# Mechanics.net
KiCad netlist of a schematic drawn in Altium Designer
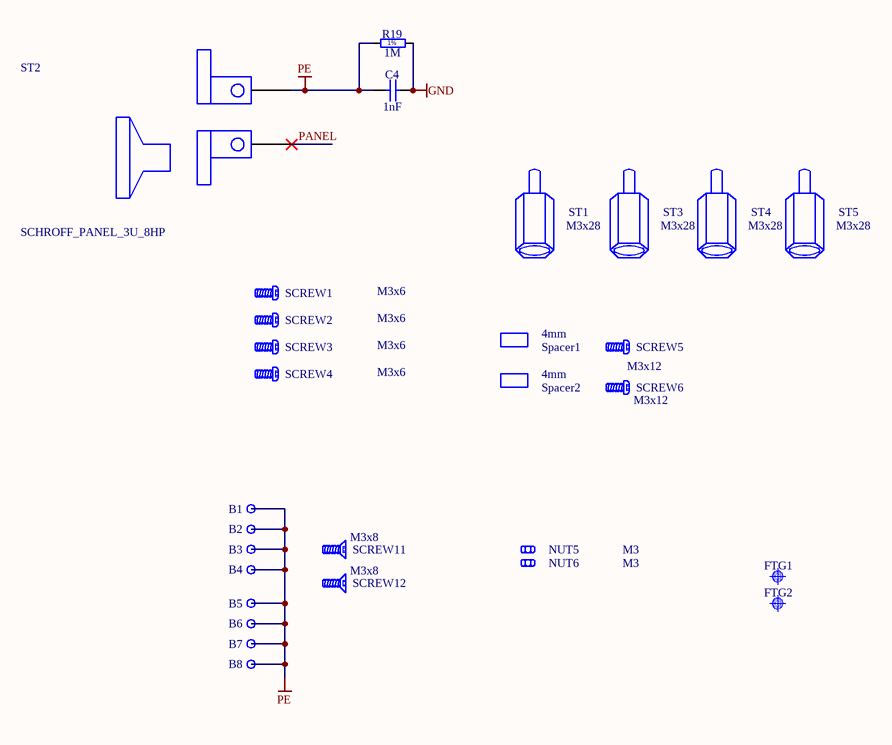
[diagram p0: Mechanics.SchDoc]

(export (version "E")
  (design (tool "Eeschema 10.0.6"))
  (components
    (comp (ref "B1")
      (value "Plated Hole")
      (footprint "MTG320_700")
      (description "Single Terminal Socket")
      (fields (field (name "PART NUMBER") "PLATED_HOLE3.2_PAD7.0") (field (name "AUTHOR") "CERN DEM JMW"))
      (libsource (lib "Eletro-mechanical") (part "Single Terminal Socket"))
    )
    (comp (ref "B2")
      (value "Plated Hole")
      (footprint "MTG320_700")
      (description "Single Terminal Socket")
      (fields (field (name "PART NUMBER") "PLATED_HOLE3.2_PAD7.0") (field (name "AUTHOR") "CERN DEM JMW"))
      (libsource (lib "Eletro-mechanical") (part "Single Terminal Socket"))
    )
    (comp (ref "B3")
      (value "Plated Hole")
      (footprint "MTG320_700")
      (description "Single Terminal Socket")
      (fields (field (name "PART NUMBER") "PLATED_HOLE3.2_PAD7.0") (field (name "AUTHOR") "CERN DEM JMW"))
      (libsource (lib "Eletro-mechanical") (part "Single Terminal Socket"))
    )
    (comp (ref "B4")
      (value "Plated Hole")
      (footprint "MTG320_700")
      (description "Single Terminal Socket")
      (fields (field (name "PART NUMBER") "PLATED_HOLE3.2_PAD7.0") (field (name "AUTHOR") "CERN DEM JMW"))
      (libsource (lib "Eletro-mechanical") (part "Single Terminal Socket"))
    )
    (comp (ref "B5")
      (value "Plated Hole")
      (footprint "MTG350_650")
      (description "Single Terminal Socket")
      (fields (field (name "PART NUMBER") "PLATED_HOLE3.5_PAD6.5") (field (name "AUTHOR") "CERN DEM JLC"))
      (libsource (lib "Eletro-mechanical") (part "Single Terminal Socket"))
    )
    (comp (ref "B6")
      (value "Plated Hole")
      (footprint "MTG350_650")
      (description "Single Terminal Socket")
      (fields (field (name "PART NUMBER") "PLATED_HOLE3.5_PAD6.5") (field (name "AUTHOR") "CERN DEM JLC"))
      (libsource (lib "Eletro-mechanical") (part "Single Terminal Socket"))
    )
    (comp (ref "B7")
      (value "Plated Hole")
      (footprint "MTG350_650")
      (description "Single Terminal Socket")
      (fields (field (name "PART NUMBER") "PLATED_HOLE3.5_PAD6.5") (field (name "AUTHOR") "CERN DEM JLC"))
      (libsource (lib "Eletro-mechanical") (part "Single Terminal Socket"))
    )
    (comp (ref "B8")
      (value "Plated Hole")
      (footprint "MTG350_650")
      (description "Single Terminal Socket")
      (fields (field (name "PART NUMBER") "PLATED_HOLE3.5_PAD6.5") (field (name "AUTHOR") "CERN DEM JLC"))
      (libsource (lib "Eletro-mechanical") (part "Single Terminal Socket"))
    )
    (comp (ref "C4")
      (value "1nF")
      (footprint "CAPC3216X180N")
      (description "Non-polarised capacitor")
      (fields
        (field (name "PART NUMBER") "CC1206_1NF_2KV_10%_X7R")
        (field (name "VOLTAGE") "2kV")
        (field (name "AUTHOR") "CERN DEM JLC")
      )
      (libsource (lib "Capacitors") (part "Capacitor - non polarized"))
    )
    (comp (ref "FTG1")
      (value "Use only in PCB")
      (footprint "FIDUCIAL_TOP_C100-200")
      (description "Fiducial Target")
      (fields (field (name "PART NUMBER") "FIDUCIAL_TARGET_C100-200") (field (name "AUTHOR") "CERN DEM JLC"))
      (libsource (lib "Eletro-mechanical") (part "Fiducial Target"))
    )
    (comp (ref "FTG2")
      (value "Use only in PCB")
      (footprint "FIDUCIAL_TOP_S100-200")
      (description "Fiducial Target")
      (fields (field (name "PART NUMBER") "FIDUCIAL_TARGET_S100-200") (field (name "AUTHOR") "CERN DEM JLC"))
      (libsource (lib "Eletro-mechanical") (part "Fiducial Target"))
    )
    (comp (ref "NUT5")
      (value "M3")
      (footprint "BOSSARD_BN628-1241443_v")
      (description "Nut")
      (fields
        (field (name "PART NUMBER") "BOSSARD_BN628-1241443_v")
        (field (name "MANUFACTURER") "BOSSARD")
        (field (name "AUTHOR") "CERN DEM JMW")
      )
      (libsource (lib "Eletro-mechanical") (part "Nut"))
    )
    (comp (ref "NUT6")
      (value "M3")
      (footprint "BOSSARD_BN628-1241443_v")
      (description "Nut")
      (fields
        (field (name "PART NUMBER") "BOSSARD_BN628-1241443_v")
        (field (name "MANUFACTURER") "BOSSARD")
        (field (name "AUTHOR") "CERN DEM JMW")
      )
      (libsource (lib "Eletro-mechanical") (part "Nut"))
    )
    (comp (ref "R19")
      (value "1M")
      (footprint "RESC3216X65N")
      (description "Resistor - 1%")
      (fields
        (field (name "PART NUMBER") "R1206_1M_1%_0.25W_100PPM")
        (field (name "POWER") "0.25W")
        (field (name "AUTHOR") "CERN DEM JLC")
      )
      (libsource (lib "Resistors") (part "Resistor - 1%"))
    )
    (comp (ref "SCREW1")
      (value "M3x6")
      (footprint "BOSSARD_BN5687-3061605_v")
      (description "Screw")
      (fields
        (field (name "PART NUMBER") "BOSSARD_BN5687-3061605_v")
        (field (name "MANUFACTURER") "BOSSARD")
        (field (name "AUTHOR") "CERN DEM JLC")
      )
      (libsource (lib "Eletro-mechanical") (part "Screw"))
    )
    (comp (ref "SCREW2")
      (value "M3x6")
      (footprint "BOSSARD_BN5687-3061605_v")
      (description "Screw")
      (fields
        (field (name "PART NUMBER") "BOSSARD_BN5687-3061605_v")
        (field (name "MANUFACTURER") "BOSSARD")
        (field (name "AUTHOR") "CERN DEM JLC")
      )
      (libsource (lib "Eletro-mechanical") (part "Screw"))
    )
    (comp (ref "SCREW3")
      (value "M3x6")
      (footprint "BOSSARD_BN5687-3061605_v")
      (description "Screw")
      (fields
        (field (name "PART NUMBER") "BOSSARD_BN5687-3061605_v")
        (field (name "MANUFACTURER") "BOSSARD")
        (field (name "AUTHOR") "CERN DEM JLC")
      )
      (libsource (lib "Eletro-mechanical") (part "Screw"))
    )
    (comp (ref "SCREW4")
      (value "M3x6")
      (footprint "BOSSARD_BN5687-3061605_v")
      (description "Screw")
      (fields
        (field (name "PART NUMBER") "BOSSARD_BN5687-3061605_v")
        (field (name "MANUFACTURER") "BOSSARD")
        (field (name "AUTHOR") "CERN DEM JLC")
      )
      (libsource (lib "Eletro-mechanical") (part "Screw"))
    )
    (comp (ref "SCREW5")
      (value "M3x12")
      (footprint "BOSSARD_BN5687-3061609_v")
      (description "Screw")
      (fields
        (field (name "PART NUMBER") "BOSSARD_BN5687-3061609_v")
        (field (name "MANUFACTURER") "BOSSARD")
        (field (name "AUTHOR") "CERN DEM JLC")
      )
      (libsource (lib "Eletro-mechanical") (part "Screw"))
    )
    (comp (ref "SCREW6")
      (value "M3x12")
      (footprint "BOSSARD_BN5687-3061609_v")
      (description "Screw")
      (fields
        (field (name "PART NUMBER") "BOSSARD_BN5687-3061609_v")
        (field (name "MANUFACTURER") "BOSSARD")
        (field (name "AUTHOR") "CERN DEM JLC")
      )
      (libsource (lib "Eletro-mechanical") (part "Screw"))
    )
    (comp (ref "SCREW11")
      (value "M3x8")
      (footprint "OSSARD_M3X8/BN3327_h")
      (description "Screw; 3x8; Head: countersunk; Pozidriv; A2 stainless steel")
      (fields
        (field (name "PART NUMBER") "OSSARD_M3X8/BN3327")
        (field (name "MANUFACTURER") "BOSSARD")
        (field (name "AUTHOR") "GK")
      )
      (libsource (lib "Mechanical") (part "Screw_M3x8_Countersunk"))
    )
    (comp (ref "SCREW12")
      (value "M3x8")
      (footprint "OSSARD_M3X8/BN3327_h")
      (description "Screw; 3x8; Head: countersunk; Pozidriv; A2 stainless steel")
      (fields
        (field (name "PART NUMBER") "OSSARD_M3X8/BN3327")
        (field (name "MANUFACTURER") "BOSSARD")
        (field (name "AUTHOR") "GK")
      )
      (libsource (lib "Mechanical") (part "Screw_M3x8_Countersunk"))
    )
    (comp (ref "Spacer1")
      (value "4mm")
      (footprint "DREMEC_DR316/3.2X4")
      (fields
        (field (name "PART NUMBER") "DREMEC_DR316/3.2X4")
        (field (name "MANUFACTURER") "DREMEC")
        (field (name "MANUFACTURER PART NUMBER") "DR316/3.2X4")
        (field (name "AUTHOR") "GK")
      )
      (libsource (lib "Mechanical") (part "MECH_Spacer_3.2x4x6"))
    )
    (comp (ref "Spacer2")
      (value "4mm")
      (footprint "DREMEC_DR316/3.2X4")
      (fields
        (field (name "PART NUMBER") "DREMEC_DR316/3.2X4")
        (field (name "MANUFACTURER") "DREMEC")
        (field (name "MANUFACTURER PART NUMBER") "DR316/3.2X4")
        (field (name "AUTHOR") "GK")
      )
      (libsource (lib "Mechanical") (part "MECH_Spacer_3.2x4x6"))
    )
    (comp (ref "ST1")
      (value "M3x28")
      (footprint "Ettinger-M3X28_05.13.281_rev")
      (description "M3x28 standoff")
      (fields
        (field (name "PART NUMBER") "Ettinger_05.13.281")
        (field (name "MANUFACTURER") "Ettinger")
        (field (name "AUTHOR") "GK")
      )
      (libsource (lib "Mechanical") (part "MECH_Standoff_M3x28_rev"))
    )
    (comp (ref "ST2")
      (value "SCHROFF_PANEL_3U_8HP")
      (footprint "Schroff 30848430")
      (description "Schroff 8HP 4U EUROCARD Panel with ejector")
      (fields (field (name "MANUFACTURER PART NUMBER") "30848430"))
      (libsource (lib "Integrated_Library_LOADER") (part "SCHROFF_PANEL_3U_8HP"))
    )
    (comp (ref "ST3")
      (value "M3x28")
      (footprint "Ettinger-M3X28_05.13.281_rev")
      (description "M3x28 standoff")
      (fields
        (field (name "PART NUMBER") "Ettinger_05.13.281")
        (field (name "MANUFACTURER") "Ettinger")
        (field (name "AUTHOR") "GK")
      )
      (libsource (lib "Mechanical") (part "MECH_Standoff_M3x28_rev"))
    )
    (comp (ref "ST4")
      (value "M3x28")
      (footprint "Ettinger-M3X28_05.13.281_rev")
      (description "M3x28 standoff")
      (fields
        (field (name "PART NUMBER") "Ettinger_05.13.281")
        (field (name "MANUFACTURER") "Ettinger")
        (field (name "AUTHOR") "GK")
      )
      (libsource (lib "Mechanical") (part "MECH_Standoff_M3x28_rev"))
    )
    (comp (ref "ST5")
      (value "M3x28")
      (footprint "Ettinger-M3X28_05.13.281_rev")
      (description "M3x28 standoff")
      (fields
        (field (name "PART NUMBER") "Ettinger_05.13.281")
        (field (name "MANUFACTURER") "Ettinger")
        (field (name "AUTHOR") "GK")
      )
      (libsource (lib "Mechanical") (part "MECH_Standoff_M3x28_rev"))
    )
  )
  (nets
    (net (code "1") (name "/PANEL") (class "Default")
      (node (ref "ST2") (pin "2") (pinfunction "2_2") (pintype "passive+no_connect"))
    )
    (net (code "2") (name "GND") (class "Default")
      (node (ref "C4") (pin "2") (pinfunction "2_2") (pintype "passive"))
      (node (ref "R19") (pin "2") (pinfunction "2_2") (pintype "passive"))
    )
    (net (code "3") (name "PE") (class "Default")
      (node (ref "B1") (pin "1") (pinfunction "1_1") (pintype "bidirectional"))
      (node (ref "B2") (pin "1") (pinfunction "1_1") (pintype "bidirectional"))
      (node (ref "B3") (pin "1") (pinfunction "1_1") (pintype "bidirectional"))
      (node (ref "B4") (pin "1") (pinfunction "1_1") (pintype "bidirectional"))
      (node (ref "B5") (pin "1") (pinfunction "1_1") (pintype "bidirectional"))
      (node (ref "B6") (pin "1") (pinfunction "1_1") (pintype "bidirectional"))
      (node (ref "B7") (pin "1") (pinfunction "1_1") (pintype "bidirectional"))
      (node (ref "B8") (pin "1") (pinfunction "1_1") (pintype "bidirectional"))
      (node (ref "C4") (pin "1") (pinfunction "1_1") (pintype "passive"))
      (node (ref "R19") (pin "1") (pinfunction "1_1") (pintype "passive"))
      (node (ref "ST2") (pin "1") (pinfunction "1_1") (pintype "passive"))
    )
  )
)
